# VCO_knobs_and_jacks_edited.net
KiCad netlist of a schematic drawn in EAGLE
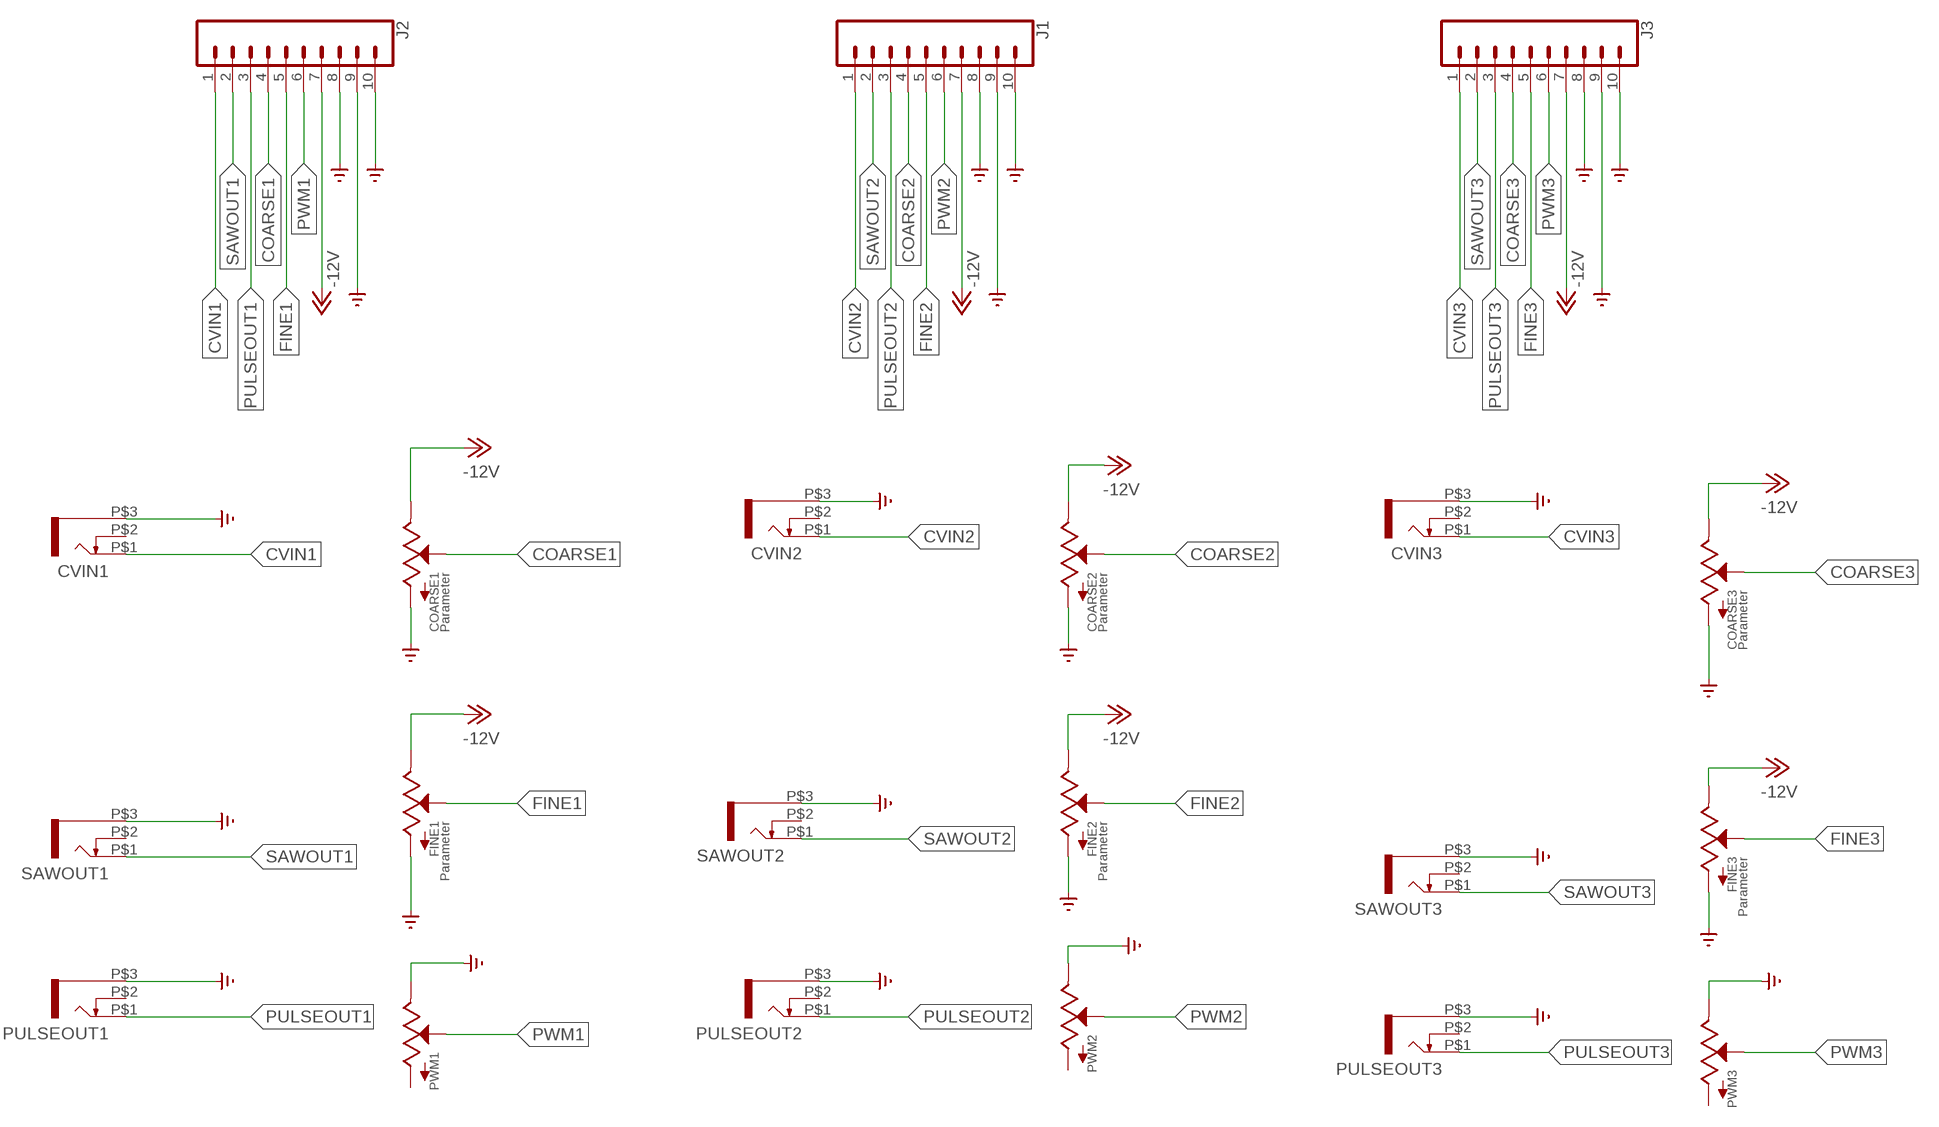
[diagram p0: schematic, sheet 1]

(export (version "E")
  (design (tool "Eeschema 10.0.6"))
  (components
    (comp (ref "COARSE1")
      (value "POTZEPHPOT")
      (footprint "eagle-import:OG-POTS_ALPS_POT_VERTICAL")
      (fields (field (name "DESC") "Parameter"))
      (libsource (lib "eagle-import") (part "POTZEPHPOT"))
    )
    (comp (ref "COARSE2")
      (value "POTZEPHPOT")
      (footprint "eagle-import:OG-POTS_ALPS_POT_VERTICAL")
      (fields (field (name "DESC") "Parameter"))
      (libsource (lib "eagle-import") (part "POTZEPHPOT"))
    )
    (comp (ref "COARSE3")
      (value "POTZEPHPOT")
      (footprint "eagle-import:OG-POTS_ALPS_POT_VERTICAL")
      (fields (field (name "DESC") "Parameter"))
      (libsource (lib "eagle-import") (part "POTZEPHPOT"))
    )
    (comp (ref "CVIN1")
      (value "WQP-PJ301M-12_JACK")
      (footprint "eagle-import:WQP-PJ301M-12_JACK")
      (libsource (lib "eagle-import") (part "WQP-PJ301M-12_JACK"))
    )
    (comp (ref "CVIN2")
      (value "WQP-PJ301M-12_JACK")
      (footprint "eagle-import:WQP-PJ301M-12_JACK")
      (libsource (lib "eagle-import") (part "WQP-PJ301M-12_JACK"))
    )
    (comp (ref "CVIN3")
      (value "WQP-PJ301M-12_JACK")
      (footprint "eagle-import:WQP-PJ301M-12_JACK")
      (libsource (lib "eagle-import") (part "WQP-PJ301M-12_JACK"))
    )
    (comp (ref "FINE1")
      (value "POTZEPHPOT")
      (footprint "eagle-import:OG-POTS_ALPS_POT_VERTICAL")
      (fields (field (name "DESC") "Parameter"))
      (libsource (lib "eagle-import") (part "POTZEPHPOT"))
    )
    (comp (ref "FINE2")
      (value "POTZEPHPOT")
      (footprint "eagle-import:OG-POTS_ALPS_POT_VERTICAL")
      (fields (field (name "DESC") "Parameter"))
      (libsource (lib "eagle-import") (part "POTZEPHPOT"))
    )
    (comp (ref "FINE3")
      (value "POTZEPHPOT")
      (footprint "eagle-import:OG-POTS_ALPS_POT_VERTICAL")
      (fields (field (name "DESC") "Parameter"))
      (libsource (lib "eagle-import") (part "POTZEPHPOT"))
    )
    (comp (ref "J1")
      (value "CONN_10\"")
      (footprint "eagle-import:1X10")
      (libsource (lib "eagle-import") (part "CONN_10{dblquote}"))
    )
    (comp (ref "J2")
      (value "CONN_10\"")
      (footprint "eagle-import:1X10")
      (libsource (lib "eagle-import") (part "CONN_10{dblquote}"))
    )
    (comp (ref "J3")
      (value "CONN_10\"")
      (footprint "eagle-import:1X10")
      (libsource (lib "eagle-import") (part "CONN_10{dblquote}"))
    )
    (comp (ref "PULSEOUT1")
      (value "WQP-PJ301M-12_JACK")
      (footprint "eagle-import:WQP-PJ301M-12_JACK")
      (libsource (lib "eagle-import") (part "WQP-PJ301M-12_JACK"))
    )
    (comp (ref "PULSEOUT2")
      (value "WQP-PJ301M-12_JACK")
      (footprint "eagle-import:WQP-PJ301M-12_JACK")
      (libsource (lib "eagle-import") (part "WQP-PJ301M-12_JACK"))
    )
    (comp (ref "PULSEOUT3")
      (value "WQP-PJ301M-12_JACK")
      (footprint "eagle-import:WQP-PJ301M-12_JACK")
      (libsource (lib "eagle-import") (part "WQP-PJ301M-12_JACK"))
    )
    (comp (ref "PWM1")
      (value "POTZEPHPOT")
      (footprint "eagle-import:OG-POTS_ALPS_POT_VERTICAL")
      (libsource (lib "eagle-import") (part "POTZEPHPOT"))
    )
    (comp (ref "PWM2")
      (value "POTZEPHPOT")
      (footprint "eagle-import:OG-POTS_ALPS_POT_VERTICAL")
      (libsource (lib "eagle-import") (part "POTZEPHPOT"))
    )
    (comp (ref "PWM3")
      (value "POTZEPHPOT")
      (footprint "eagle-import:OG-POTS_ALPS_POT_VERTICAL")
      (libsource (lib "eagle-import") (part "POTZEPHPOT"))
    )
    (comp (ref "SAWOUT1")
      (value "WQP-PJ301M-12_JACK")
      (footprint "eagle-import:WQP-PJ301M-12_JACK")
      (libsource (lib "eagle-import") (part "WQP-PJ301M-12_JACK"))
    )
    (comp (ref "SAWOUT2")
      (value "WQP-PJ301M-12_JACK")
      (footprint "eagle-import:WQP-PJ301M-12_JACK")
      (libsource (lib "eagle-import") (part "WQP-PJ301M-12_JACK"))
    )
    (comp (ref "SAWOUT3")
      (value "WQP-PJ301M-12_JACK")
      (footprint "eagle-import:WQP-PJ301M-12_JACK")
      (libsource (lib "eagle-import") (part "WQP-PJ301M-12_JACK"))
    )
  )
  (nets
    (net (code "1") (name "-12V") (class "Default")
      (node (ref "COARSE1") (pin "P$1") (pinfunction "E_P$1") (pintype "passive"))
      (node (ref "COARSE2") (pin "P$1") (pinfunction "E_P$1") (pintype "passive"))
      (node (ref "COARSE3") (pin "P$1") (pinfunction "E_P$1") (pintype "passive"))
      (node (ref "FINE1") (pin "P$1") (pinfunction "E_P$1") (pintype "passive"))
      (node (ref "FINE2") (pin "P$1") (pinfunction "E_P$1") (pintype "passive"))
      (node (ref "FINE3") (pin "P$1") (pinfunction "E_P$1") (pintype "passive"))
      (node (ref "J1") (pin "7") (pinfunction "7_7") (pintype "passive"))
      (node (ref "J2") (pin "7") (pinfunction "7_7") (pintype "passive"))
      (node (ref "J3") (pin "7") (pinfunction "7_7") (pintype "passive"))
    )
    (net (code "2") (name "COARSE1") (class "Default")
      (node (ref "COARSE1") (pin "P$2") (pinfunction "S_P$2") (pintype "passive"))
      (node (ref "J2") (pin "4") (pinfunction "4_4") (pintype "passive"))
    )
    (net (code "3") (name "COARSE2") (class "Default")
      (node (ref "COARSE2") (pin "P$2") (pinfunction "S_P$2") (pintype "passive"))
      (node (ref "J1") (pin "4") (pinfunction "4_4") (pintype "passive"))
    )
    (net (code "4") (name "COARSE3") (class "Default")
      (node (ref "COARSE3") (pin "P$2") (pinfunction "S_P$2") (pintype "passive"))
      (node (ref "J3") (pin "4") (pinfunction "4_4") (pintype "passive"))
    )
    (net (code "5") (name "CVIN1") (class "Default")
      (node (ref "CVIN1") (pin "P$1") (pinfunction "2_P$1") (pintype "passive"))
      (node (ref "J2") (pin "1") (pinfunction "1_1") (pintype "passive"))
    )
    (net (code "6") (name "CVIN2") (class "Default")
      (node (ref "CVIN2") (pin "P$1") (pinfunction "2_P$1") (pintype "passive"))
      (node (ref "J1") (pin "1") (pinfunction "1_1") (pintype "passive"))
    )
    (net (code "7") (name "CVIN3") (class "Default")
      (node (ref "CVIN3") (pin "P$1") (pinfunction "2_P$1") (pintype "passive"))
      (node (ref "J3") (pin "1") (pinfunction "1_1") (pintype "passive"))
    )
    (net (code "8") (name "FINE1") (class "Default")
      (node (ref "FINE1") (pin "P$2") (pinfunction "S_P$2") (pintype "passive"))
      (node (ref "J2") (pin "5") (pinfunction "5_5") (pintype "passive"))
    )
    (net (code "9") (name "FINE2") (class "Default")
      (node (ref "FINE2") (pin "P$2") (pinfunction "S_P$2") (pintype "passive"))
      (node (ref "J1") (pin "5") (pinfunction "5_5") (pintype "passive"))
    )
    (net (code "10") (name "FINE3") (class "Default")
      (node (ref "FINE3") (pin "P$2") (pinfunction "S_P$2") (pintype "passive"))
      (node (ref "J3") (pin "5") (pinfunction "5_5") (pintype "passive"))
    )
    (net (code "11") (name "PULSEOUT1") (class "Default")
      (node (ref "J2") (pin "3") (pinfunction "3_3") (pintype "passive"))
      (node (ref "PULSEOUT1") (pin "P$1") (pinfunction "2_P$1") (pintype "passive"))
    )
    (net (code "12") (name "PULSEOUT2") (class "Default")
      (node (ref "J1") (pin "3") (pinfunction "3_3") (pintype "passive"))
      (node (ref "PULSEOUT2") (pin "P$1") (pinfunction "2_P$1") (pintype "passive"))
    )
    (net (code "13") (name "PULSEOUT3") (class "Default")
      (node (ref "J3") (pin "3") (pinfunction "3_3") (pintype "passive"))
      (node (ref "PULSEOUT3") (pin "P$1") (pinfunction "2_P$1") (pintype "passive"))
    )
    (net (code "14") (name "PWM1") (class "Default")
      (node (ref "J2") (pin "6") (pinfunction "6_6") (pintype "passive"))
      (node (ref "PWM1") (pin "P$2") (pinfunction "S_P$2") (pintype "passive"))
    )
    (net (code "15") (name "PWM2") (class "Default")
      (node (ref "J1") (pin "6") (pinfunction "6_6") (pintype "passive"))
      (node (ref "PWM2") (pin "P$2") (pinfunction "S_P$2") (pintype "passive"))
    )
    (net (code "16") (name "PWM3") (class "Default")
      (node (ref "J3") (pin "6") (pinfunction "6_6") (pintype "passive"))
      (node (ref "PWM3") (pin "P$2") (pinfunction "S_P$2") (pintype "passive"))
    )
    (net (code "17") (name "SAWOUT1") (class "Default")
      (node (ref "J2") (pin "2") (pinfunction "2_2") (pintype "passive"))
      (node (ref "SAWOUT1") (pin "P$1") (pinfunction "2_P$1") (pintype "passive"))
    )
    (net (code "18") (name "SAWOUT2") (class "Default")
      (node (ref "J1") (pin "2") (pinfunction "2_2") (pintype "passive"))
      (node (ref "SAWOUT2") (pin "P$1") (pinfunction "2_P$1") (pintype "passive"))
    )
    (net (code "19") (name "SAWOUT3") (class "Default")
      (node (ref "J3") (pin "2") (pinfunction "2_2") (pintype "passive"))
      (node (ref "SAWOUT3") (pin "P$1") (pinfunction "2_P$1") (pintype "passive"))
    )
    (net (code "20") (name "SUPPLY0_GND_") (class "Default")
      (node (ref "COARSE1") (pin "P$3") (pinfunction "A_P$3") (pintype "passive"))
      (node (ref "COARSE2") (pin "P$3") (pinfunction "A_P$3") (pintype "passive"))
      (node (ref "COARSE3") (pin "P$3") (pinfunction "A_P$3") (pintype "passive"))
      (node (ref "CVIN1") (pin "P$3") (pinfunction "1_P$3") (pintype "passive"))
      (node (ref "CVIN2") (pin "P$3") (pinfunction "1_P$3") (pintype "passive"))
      (node (ref "CVIN3") (pin "P$3") (pinfunction "1_P$3") (pintype "passive"))
      (node (ref "FINE1") (pin "P$3") (pinfunction "A_P$3") (pintype "passive"))
      (node (ref "FINE2") (pin "P$3") (pinfunction "A_P$3") (pintype "passive"))
      (node (ref "FINE3") (pin "P$3") (pinfunction "A_P$3") (pintype "passive"))
      (node (ref "J1") (pin "10") (pinfunction "10_10") (pintype "passive"))
      (node (ref "J1") (pin "8") (pinfunction "8_8") (pintype "passive"))
      (node (ref "J1") (pin "9") (pinfunction "9_9") (pintype "passive"))
      (node (ref "J2") (pin "10") (pinfunction "10_10") (pintype "passive"))
      (node (ref "J2") (pin "8") (pinfunction "8_8") (pintype "passive"))
      (node (ref "J2") (pin "9") (pinfunction "9_9") (pintype "passive"))
      (node (ref "J3") (pin "10") (pinfunction "10_10") (pintype "passive"))
      (node (ref "J3") (pin "8") (pinfunction "8_8") (pintype "passive"))
      (node (ref "J3") (pin "9") (pinfunction "9_9") (pintype "passive"))
      (node (ref "PULSEOUT1") (pin "P$3") (pinfunction "1_P$3") (pintype "passive"))
      (node (ref "PULSEOUT2") (pin "P$3") (pinfunction "1_P$3") (pintype "passive"))
      (node (ref "PULSEOUT3") (pin "P$3") (pinfunction "1_P$3") (pintype "passive"))
      (node (ref "PWM1") (pin "P$1") (pinfunction "E_P$1") (pintype "passive"))
      (node (ref "PWM2") (pin "P$1") (pinfunction "E_P$1") (pintype "passive"))
      (node (ref "PWM3") (pin "P$1") (pinfunction "E_P$1") (pintype "passive"))
      (node (ref "SAWOUT1") (pin "P$3") (pinfunction "1_P$3") (pintype "passive"))
      (node (ref "SAWOUT2") (pin "P$3") (pinfunction "1_P$3") (pintype "passive"))
      (node (ref "SAWOUT3") (pin "P$3") (pinfunction "1_P$3") (pintype "passive"))
    )
    (net (code "21") (name "unconnected-(CVIN1-3-PadP$2)") (class "Default")
      (node (ref "CVIN1") (pin "P$2") (pinfunction "3_P$2") (pintype "passive"))
    )
    (net (code "22") (name "unconnected-(CVIN2-3-PadP$2)") (class "Default")
      (node (ref "CVIN2") (pin "P$2") (pinfunction "3_P$2") (pintype "passive"))
    )
    (net (code "23") (name "unconnected-(CVIN3-3-PadP$2)") (class "Default")
      (node (ref "CVIN3") (pin "P$2") (pinfunction "3_P$2") (pintype "passive"))
    )
    (net (code "24") (name "unconnected-(PULSEOUT1-3-PadP$2)") (class "Default")
      (node (ref "PULSEOUT1") (pin "P$2") (pinfunction "3_P$2") (pintype "passive"))
    )
    (net (code "25") (name "unconnected-(PULSEOUT2-3-PadP$2)") (class "Default")
      (node (ref "PULSEOUT2") (pin "P$2") (pinfunction "3_P$2") (pintype "passive"))
    )
    (net (code "26") (name "unconnected-(PULSEOUT3-3-PadP$2)") (class "Default")
      (node (ref "PULSEOUT3") (pin "P$2") (pinfunction "3_P$2") (pintype "passive"))
    )
    (net (code "27") (name "unconnected-(PWM1-A-PadP$3)") (class "Default")
      (node (ref "PWM1") (pin "P$3") (pinfunction "A_P$3") (pintype "passive"))
    )
    (net (code "28") (name "unconnected-(PWM2-A-PadP$3)") (class "Default")
      (node (ref "PWM2") (pin "P$3") (pinfunction "A_P$3") (pintype "passive"))
    )
    (net (code "29") (name "unconnected-(PWM3-A-PadP$3)") (class "Default")
      (node (ref "PWM3") (pin "P$3") (pinfunction "A_P$3") (pintype "passive"))
    )
    (net (code "30") (name "unconnected-(SAWOUT1-3-PadP$2)") (class "Default")
      (node (ref "SAWOUT1") (pin "P$2") (pinfunction "3_P$2") (pintype "passive"))
    )
    (net (code "31") (name "unconnected-(SAWOUT2-3-PadP$2)") (class "Default")
      (node (ref "SAWOUT2") (pin "P$2") (pinfunction "3_P$2") (pintype "passive"))
    )
    (net (code "32") (name "unconnected-(SAWOUT3-3-PadP$2)") (class "Default")
      (node (ref "SAWOUT3") (pin "P$2") (pinfunction "3_P$2") (pintype "passive"))
    )
  )
)
